# power.net
KiCad netlist of a schematic drawn in Altium Designer
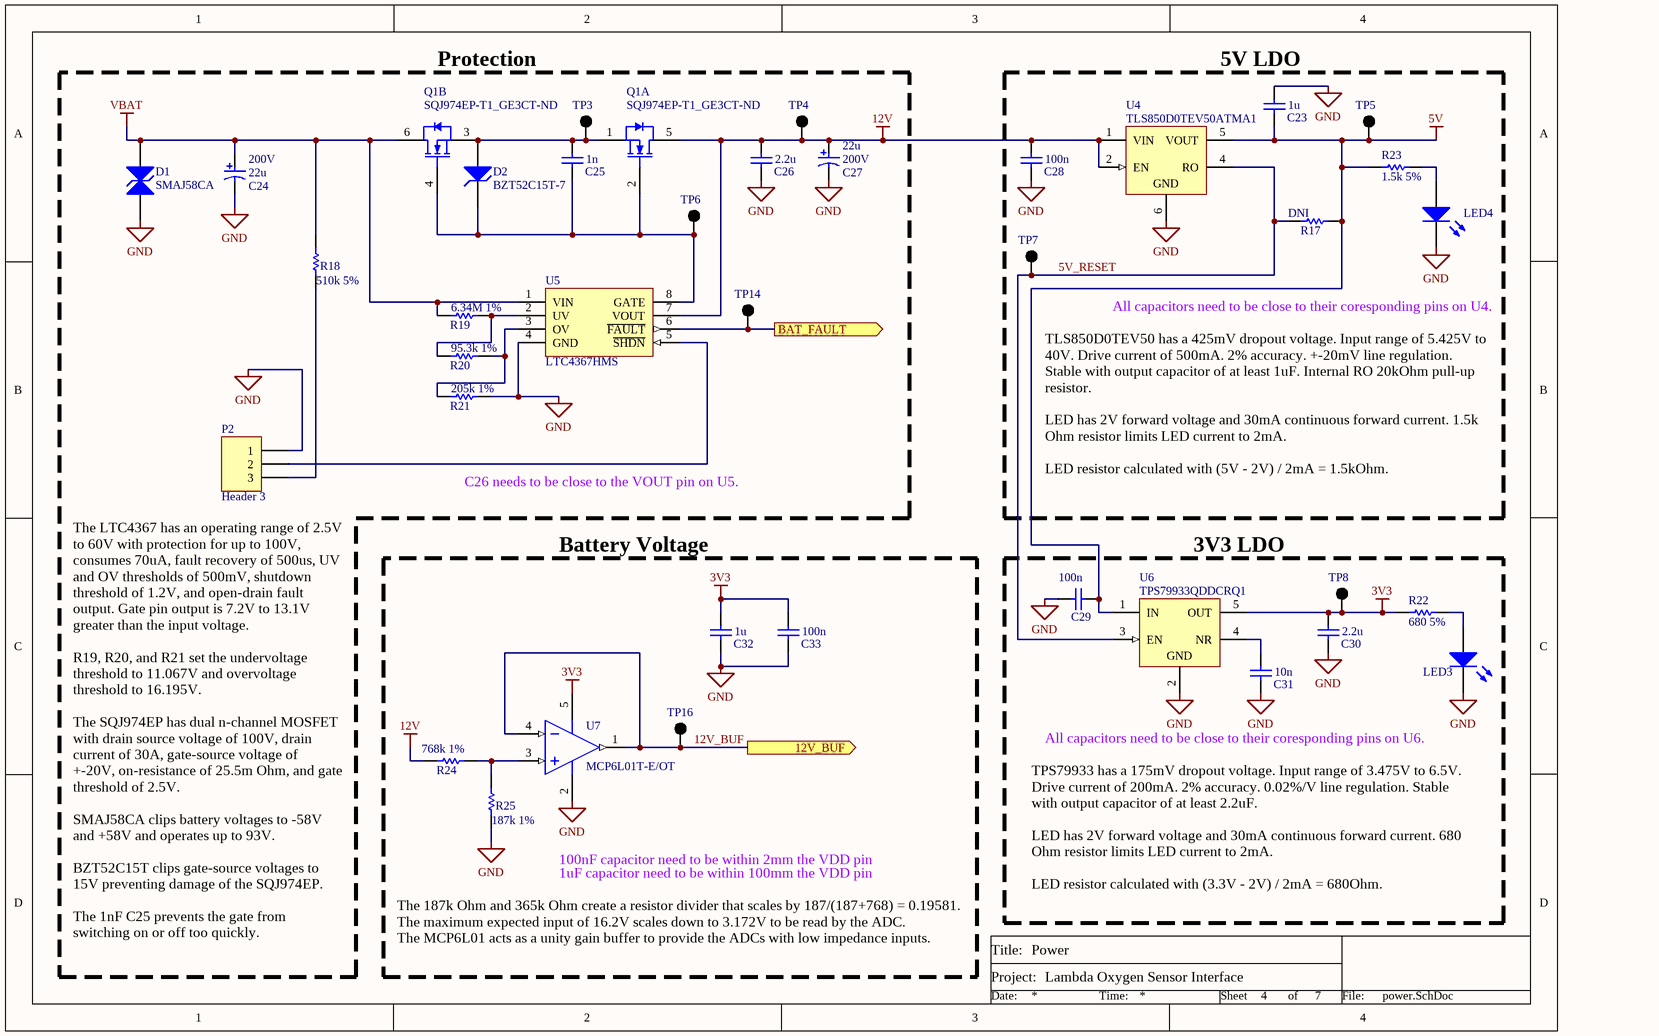
[diagram p0: power.SchDoc]

(export (version "E")
  (design (tool "Eeschema 10.0.6"))
  (components
    (comp (ref "C23")
      (value "1u")
      (footprint "1206")
      (description "Generic 1206 Capacitor")
      (libsource (lib "symbol_library") (part "C_1206"))
    )
    (comp (ref "C24")
      (value "22u")
      (footprint "NIC-UUX2A470MNL1GS_M")
      (description "Generic PCAP_10x10 Can Aluminum Electrolytic Capacitor")
      (fields (field (name "VOLTAGE") "200V") (field (name "Comment") "Generic Electrolytic Capacitor"))
      (libsource (lib "symbol_library") (part "C_can"))
    )
    (comp (ref "C25")
      (value "1n")
      (footprint "0805")
      (description "Generic 0805 Capacitor")
      (libsource (lib "symbol_library") (part "C_0805"))
    )
    (comp (ref "C26")
      (value "2.2u")
      (footprint "1206")
      (description "Generic 1206 Capacitor")
      (libsource (lib "symbol_library") (part "C_1206"))
    )
    (comp (ref "C27")
      (value "22u")
      (footprint "NIC-UUX2A470MNL1GS_M")
      (description "Generic PCAP_10x10 Can Aluminum Electrolytic Capacitor")
      (fields (field (name "VOLTAGE") "200V") (field (name "Comment") "Generic Electrolytic Capacitor"))
      (libsource (lib "symbol_library") (part "C_can"))
    )
    (comp (ref "C28")
      (value "100n")
      (footprint "0805")
      (description "Generic 0805 Capacitor")
      (libsource (lib "symbol_library") (part "C_0805"))
    )
    (comp (ref "C29")
      (value "100n")
      (footprint "0805")
      (description "Generic 0805 Capacitor")
      (libsource (lib "symbol_library") (part "C_0805"))
    )
    (comp (ref "C30")
      (value "2.2u")
      (footprint "1206")
      (description "Generic 1206 Capacitor")
      (libsource (lib "symbol_library") (part "C_1206"))
    )
    (comp (ref "C31")
      (value "10n")
      (footprint "0805")
      (description "Generic 0805 Capacitor")
      (libsource (lib "symbol_library") (part "C_0805"))
    )
    (comp (ref "C32")
      (value "1u")
      (footprint "1206")
      (description "Generic 1206 Capacitor")
      (libsource (lib "symbol_library") (part "C_1206"))
    )
    (comp (ref "C33")
      (value "100n")
      (footprint "0805")
      (description "Generic 0805 Capacitor")
      (libsource (lib "symbol_library") (part "C_0805"))
    )
    (comp (ref "D1")
      (value "SMAJ58CA")
      (footprint "VISH-DO-214AC-2_M")
      (fields
        (field (name "MANUFACTURER") "Vishay Semiconductor")
        (field (name "PARTNUMBER") "SMAJ58CA-E3/5A")
      )
      (libsource (lib "symbol_library") (part "SMAJ58CA"))
    )
    (comp (ref "D2")
      (value "BZT52C15T-7")
      (footprint "DIOD-SOD523-2_V")
      (description "Zener Diode 15V 300mW ±6% Surface Mount SOD-523")
      (fields (field (name "MANUFACTURER") "Diodes Inc") (field (name "PARTNUMBER") "BZT52C16-7-F"))
      (libsource (lib "symbol_library") (part "BZT52C15T"))
    )
    (comp (ref "LED3")
      (value "150080SS75000")
      (footprint "0805_A")
      (description "SMD mono-color Chip LED, WL-SMCW, Super Red")
      (fields (field (name "MANUFACTURER") "Wuerth Elektronik"))
      (libsource (lib "symbol_library") (part "LED_0805"))
    )
    (comp (ref "LED4")
      (value "150080SS75000")
      (footprint "0805_A")
      (description "SMD mono-color Chip LED, WL-SMCW, Super Red")
      (fields (field (name "MANUFACTURER") "Wuerth Elektronik"))
      (libsource (lib "symbol_library") (part "LED_0805"))
    )
    (comp (ref "P2")
      (value "Header 3")
      (footprint "HDR1X3")
      (description "Header, 3-Pin")
      (fields (field (name "PUBLISHER") "Altium Limited"))
      (libsource (lib "Miscellaneous Connectors") (part "Header 3"))
    )
    (comp (ref "Q1")
      (value "SQJ974EP-T1_GE3CT-ND")
      (footprint "VISH-POWERPAKSO-8_A_V")
      (description "Mosfet Array 2 N-Channel (Dual) 100V 30A (Tc) 48W Surface Mount PowerPAK® SO-8 Dual")
      (fields (field (name "MANUFACTURER") "Vishay"))
      (libsource (lib "symbol_library") (part "SQJ974EP"))
    )
    (comp (ref "R17")
      (value "DNI")
      (footprint "0603")
      (description "Generic 0603 Resistor")
      (libsource (lib "symbol_library") (part "R_0603"))
    )
    (comp (ref "R18")
      (value "510k 5%")
      (footprint "0603")
      (description "Generic 0603 Resistor")
      (libsource (lib "symbol_library") (part "R_0603"))
    )
    (comp (ref "R19")
      (value "6.34M 1%")
      (footprint "0603")
      (description "Generic 0603 Resistor")
      (libsource (lib "symbol_library") (part "R_0603"))
    )
    (comp (ref "R20")
      (value "95.3k 1%")
      (footprint "0603")
      (description "Generic 0603 Resistor")
      (libsource (lib "symbol_library") (part "R_0603"))
    )
    (comp (ref "R21")
      (value "205k 1%")
      (footprint "0603")
      (description "Generic 0603 Resistor")
      (libsource (lib "symbol_library") (part "R_0603"))
    )
    (comp (ref "R22")
      (value "680 5%")
      (footprint "0603")
      (description "Generic 0603 Resistor")
      (libsource (lib "symbol_library") (part "R_0603"))
    )
    (comp (ref "R23")
      (value "1.5k 5%")
      (footprint "0603")
      (description "Generic 0603 Resistor")
      (libsource (lib "symbol_library") (part "R_0603"))
    )
    (comp (ref "R24")
      (value "768k 1%")
      (footprint "0603")
      (description "Generic 0603 Resistor")
      (libsource (lib "symbol_library") (part "R_0603"))
    )
    (comp (ref "R25")
      (value "187k 1%")
      (footprint "0603")
      (description "Generic 0603 Resistor")
      (libsource (lib "symbol_library") (part "R_0603"))
    )
    (comp (ref "TP3")
      (value "5001")
      (footprint "KSTN-5001")
      (description "Test Point, Black, 1-Pin THD, RoHS, Bulk")
      (fields (field (name "MANUFACTURER") "Keystone"))
      (libsource (lib "symbol_library") (part "TP5001"))
    )
    (comp (ref "TP4")
      (value "5001")
      (footprint "KSTN-5001")
      (description "Test Point, Black, 1-Pin THD, RoHS, Bulk")
      (fields (field (name "MANUFACTURER") "Keystone"))
      (libsource (lib "symbol_library") (part "TP5001"))
    )
    (comp (ref "TP5")
      (value "5001")
      (footprint "KSTN-5001")
      (description "Test Point, Black, 1-Pin THD, RoHS, Bulk")
      (fields (field (name "MANUFACTURER") "Keystone"))
      (libsource (lib "symbol_library") (part "TP5001"))
    )
    (comp (ref "TP6")
      (value "5001")
      (footprint "KSTN-5001")
      (description "Test Point, Black, 1-Pin THD, RoHS, Bulk")
      (fields (field (name "MANUFACTURER") "Keystone"))
      (libsource (lib "symbol_library") (part "TP5001"))
    )
    (comp (ref "TP7")
      (value "5001")
      (footprint "KSTN-5001")
      (description "Test Point, Black, 1-Pin THD, RoHS, Bulk")
      (fields (field (name "MANUFACTURER") "Keystone"))
      (libsource (lib "symbol_library") (part "TP5001"))
    )
    (comp (ref "TP8")
      (value "5001")
      (footprint "KSTN-5001")
      (description "Test Point, Black, 1-Pin THD, RoHS, Bulk")
      (fields (field (name "MANUFACTURER") "Keystone"))
      (libsource (lib "symbol_library") (part "TP5001"))
    )
    (comp (ref "TP14")
      (value "5001")
      (footprint "KSTN-5001")
      (description "Test Point, Black, 1-Pin THD, RoHS, Bulk")
      (fields (field (name "MANUFACTURER") "Keystone"))
      (libsource (lib "symbol_library") (part "TP5001"))
    )
    (comp (ref "TP16")
      (value "5001")
      (footprint "KSTN-5001")
      (description "Test Point, Black, 1-Pin THD, RoHS, Bulk")
      (fields (field (name "MANUFACTURER") "Keystone"))
      (libsource (lib "symbol_library") (part "TP5001"))
    )
    (comp (ref "U4")
      (value "TLS850D0TEV50ATMA1")
      (footprint "KVU0005A_M")
      (description "Linear Voltage Regulator IC  1 Output  500mA PG-TO252-5")
      (fields
        (field (name "PARTNUMBER") "TPS7A6150QKVURQ1")
        (field (name "MANUFACTURER") "Texas Instruments")
      )
      (libsource (lib "symbol_library") (part "TLS850D0TE"))
    )
    (comp (ref "U5")
      (value "LTC4367HMS")
      (footprint "MSOP8_M")
      (description "100V Overvoltage, Undervoltage and Reverse Supply Protection Controller")
      (libsource (lib "symbol_library") (part "LTC4367"))
    )
    (comp (ref "U6")
      (value "TPS79933QDDCRQ1")
      (footprint "DDC0005A_M")
      (fields (field (name "MANUFACTURER") "Texas Instruments"))
      (libsource (lib "symbol_library") (part "TPS79933"))
    )
    (comp (ref "U7")
      (value "MCP6L01T-E/OT")
      (footprint "DDC0005A_M")
      (description "1 MHz, 85 uA Op Amp, 5-Pin SOT-23, Extended Temperature Range")
      (libsource (lib "symbol_library") (part "MCP6L01"))
    )
  )
  (nets
    (net (code "1") (name "/5V_RESET") (class "Default")
      (node (ref "R17") (pin "1") (pinfunction "1_1") (pintype "passive"))
      (node (ref "TP7") (pin "1") (pintype "passive"))
      (node (ref "U4") (pin "4") (pinfunction "RO_4") (pintype "open_collector"))
      (node (ref "U6") (pin "3") (pinfunction "EN_3") (pintype "input"))
    )
    (net (code "2") (name "/12V_BUF") (class "Default")
      (node (ref "TP16") (pin "1") (pintype "passive"))
      (node (ref "U7") (pin "1") (pinfunction "VOUT_1") (pintype "output"))
      (node (ref "U7") (pin "4") (pinfunction "VIN-_4") (pintype "input"))
    )
    (net (code "3") (name "/BAT_FAULT") (class "Default")
      (node (ref "TP14") (pin "1") (pintype "passive"))
      (node (ref "U5") (pin "6") (pinfunction "~{FAULT}_6") (pintype "output"))
    )
    (net (code "4") (name "3V3") (class "Default")
      (node (ref "C30") (pin "2") (pinfunction "2_2") (pintype "passive"))
      (node (ref "C32") (pin "2") (pinfunction "2_2") (pintype "passive"))
      (node (ref "C33") (pin "2") (pinfunction "2_2") (pintype "passive"))
      (node (ref "R22") (pin "2") (pinfunction "2_2") (pintype "passive"))
      (node (ref "TP8") (pin "1") (pintype "passive"))
      (node (ref "U6") (pin "5") (pinfunction "OUT_5") (pintype "power_in"))
      (node (ref "U7") (pin "5") (pinfunction "VDD_5") (pintype "power_in"))
    )
    (net (code "5") (name "5V") (class "Default")
      (node (ref "C23") (pin "1") (pinfunction "1_1") (pintype "passive"))
      (node (ref "C29") (pin "2") (pinfunction "2_2") (pintype "passive"))
      (node (ref "R17") (pin "2") (pinfunction "2_2") (pintype "passive"))
      (node (ref "R23") (pin "2") (pinfunction "2_2") (pintype "passive"))
      (node (ref "TP5") (pin "1") (pintype "passive"))
      (node (ref "U4") (pin "5") (pinfunction "VOUT_5") (pintype "power_in"))
      (node (ref "U6") (pin "1") (pinfunction "IN_1") (pintype "power_in"))
    )
    (net (code "6") (name "12V") (class "Default")
      (node (ref "C26") (pin "2") (pinfunction "2_2") (pintype "passive"))
      (node (ref "C27") (pin "1") (pinfunction "1_1") (pintype "passive"))
      (node (ref "C28") (pin "2") (pinfunction "2_2") (pintype "passive"))
      (node (ref "Q1") (pin "5") (pinfunction "G2_5") (pintype "passive"))
      (node (ref "R24") (pin "1") (pinfunction "1_1") (pintype "passive"))
      (node (ref "TP4") (pin "1") (pintype "passive"))
      (node (ref "U4") (pin "1") (pinfunction "VIN_1") (pintype "power_in"))
      (node (ref "U4") (pin "2") (pinfunction "EN_2") (pintype "input"))
      (node (ref "U5") (pin "7") (pinfunction "VOUT_7") (pintype "passive"))
    )
    (net (code "7") (name "GND") (class "Default")
      (node (ref "C23") (pin "2") (pinfunction "2_2") (pintype "passive"))
      (node (ref "C24") (pin "2") (pinfunction "2_2") (pintype "passive"))
      (node (ref "C26") (pin "1") (pinfunction "1_1") (pintype "passive"))
      (node (ref "C27") (pin "2") (pinfunction "2_2") (pintype "passive"))
      (node (ref "C28") (pin "1") (pinfunction "1_1") (pintype "passive"))
      (node (ref "C29") (pin "1") (pinfunction "1_1") (pintype "passive"))
      (node (ref "C30") (pin "1") (pinfunction "1_1") (pintype "passive"))
      (node (ref "C31") (pin "1") (pinfunction "1_1") (pintype "passive"))
      (node (ref "C32") (pin "1") (pinfunction "1_1") (pintype "passive"))
      (node (ref "C33") (pin "1") (pinfunction "1_1") (pintype "passive"))
      (node (ref "D1") (pin "1") (pinfunction "A1_1") (pintype "passive"))
      (node (ref "LED3") (pin "1") (pinfunction "K_1") (pintype "passive"))
      (node (ref "LED4") (pin "1") (pinfunction "K_1") (pintype "passive"))
      (node (ref "P2") (pin "1") (pinfunction "1_1") (pintype "passive"))
      (node (ref "R21") (pin "2") (pinfunction "2_2") (pintype "passive"))
      (node (ref "R25") (pin "1") (pinfunction "1_1") (pintype "passive"))
      (node (ref "U4") (pin "6") (pinfunction "GND_6") (pintype "power_in"))
      (node (ref "U5") (pin "4") (pinfunction "GND_4") (pintype "power_in"))
      (node (ref "U6") (pin "2") (pinfunction "GND_2") (pintype "power_in"))
      (node (ref "U7") (pin "2") (pinfunction "VSS_2") (pintype "power_in"))
    )
    (net (code "8") (name "Net-(D2-A)") (class "Default")
      (node (ref "C25") (pin "2") (pinfunction "2_2") (pintype "passive"))
      (node (ref "D2") (pin "1") (pinfunction "A_1") (pintype "passive"))
      (node (ref "Q1") (pin "1") (pinfunction "S2_1") (pintype "passive"))
      (node (ref "Q1") (pin "3") (pinfunction "S2_3") (pintype "passive"))
      (node (ref "TP3") (pin "1") (pintype "passive"))
    )
    (net (code "9") (name "Net-(D2-K)") (class "Default")
      (node (ref "C25") (pin "1") (pinfunction "1_1") (pintype "passive"))
      (node (ref "D2") (pin "2") (pinfunction "K_2") (pintype "passive"))
      (node (ref "Q1") (pin "2") (pinfunction "G2_2") (pintype "passive"))
      (node (ref "Q1") (pin "4") (pinfunction "G2_4") (pintype "passive"))
      (node (ref "TP6") (pin "1") (pintype "passive"))
      (node (ref "U5") (pin "8") (pinfunction "GATE_8") (pintype "passive"))
    )
    (net (code "10") (name "Net-(LED3-A)") (class "Default")
      (node (ref "LED3") (pin "2") (pinfunction "A_2") (pintype "passive"))
      (node (ref "R22") (pin "1") (pinfunction "1_1") (pintype "passive"))
    )
    (net (code "11") (name "Net-(LED4-A)") (class "Default")
      (node (ref "LED4") (pin "2") (pinfunction "A_2") (pintype "passive"))
      (node (ref "R23") (pin "1") (pinfunction "1_1") (pintype "passive"))
    )
    (net (code "12") (name "Net-(P2-Pad3)") (class "Default")
      (node (ref "P2") (pin "3") (pinfunction "3_3") (pintype "passive"))
      (node (ref "R18") (pin "1") (pinfunction "1_1") (pintype "passive"))
    )
    (net (code "13") (name "Net-(U5-OV)") (class "Default")
      (node (ref "R20") (pin "2") (pinfunction "2_2") (pintype "passive"))
      (node (ref "R21") (pin "1") (pinfunction "1_1") (pintype "passive"))
      (node (ref "U5") (pin "3") (pinfunction "OV_3") (pintype "passive"))
    )
    (net (code "14") (name "Net-(U5-UV)") (class "Default")
      (node (ref "R19") (pin "2") (pinfunction "2_2") (pintype "passive"))
      (node (ref "R20") (pin "1") (pinfunction "1_1") (pintype "passive"))
      (node (ref "U5") (pin "2") (pinfunction "UV_2") (pintype "passive"))
    )
    (net (code "15") (name "Net-(U5-~{SHDN})") (class "Default")
      (node (ref "P2") (pin "2") (pinfunction "2_2") (pintype "passive"))
      (node (ref "U5") (pin "5") (pinfunction "~{SHDN}_5") (pintype "input"))
    )
    (net (code "16") (name "Net-(U6-NR)") (class "Default")
      (node (ref "C31") (pin "2") (pinfunction "2_2") (pintype "passive"))
      (node (ref "U6") (pin "4") (pinfunction "NR_4") (pintype "passive"))
    )
    (net (code "17") (name "Net-(U7-VIN+)") (class "Default")
      (node (ref "R24") (pin "2") (pinfunction "2_2") (pintype "passive"))
      (node (ref "R25") (pin "2") (pinfunction "2_2") (pintype "passive"))
      (node (ref "U7") (pin "3") (pinfunction "VIN+_3") (pintype "input"))
    )
    (net (code "18") (name "VBAT") (class "Default")
      (node (ref "C24") (pin "1") (pinfunction "1_1") (pintype "passive"))
      (node (ref "D1") (pin "2") (pinfunction "A2_2") (pintype "passive"))
      (node (ref "Q1") (pin "6") (pinfunction "G2_6") (pintype "passive"))
      (node (ref "R18") (pin "2") (pinfunction "2_2") (pintype "passive"))
      (node (ref "R19") (pin "1") (pinfunction "1_1") (pintype "passive"))
      (node (ref "U5") (pin "1") (pinfunction "VIN_1") (pintype "power_in"))
    )
  )
)
